# anemo5.net
KiCad netlist of a schematic drawn in EAGLE
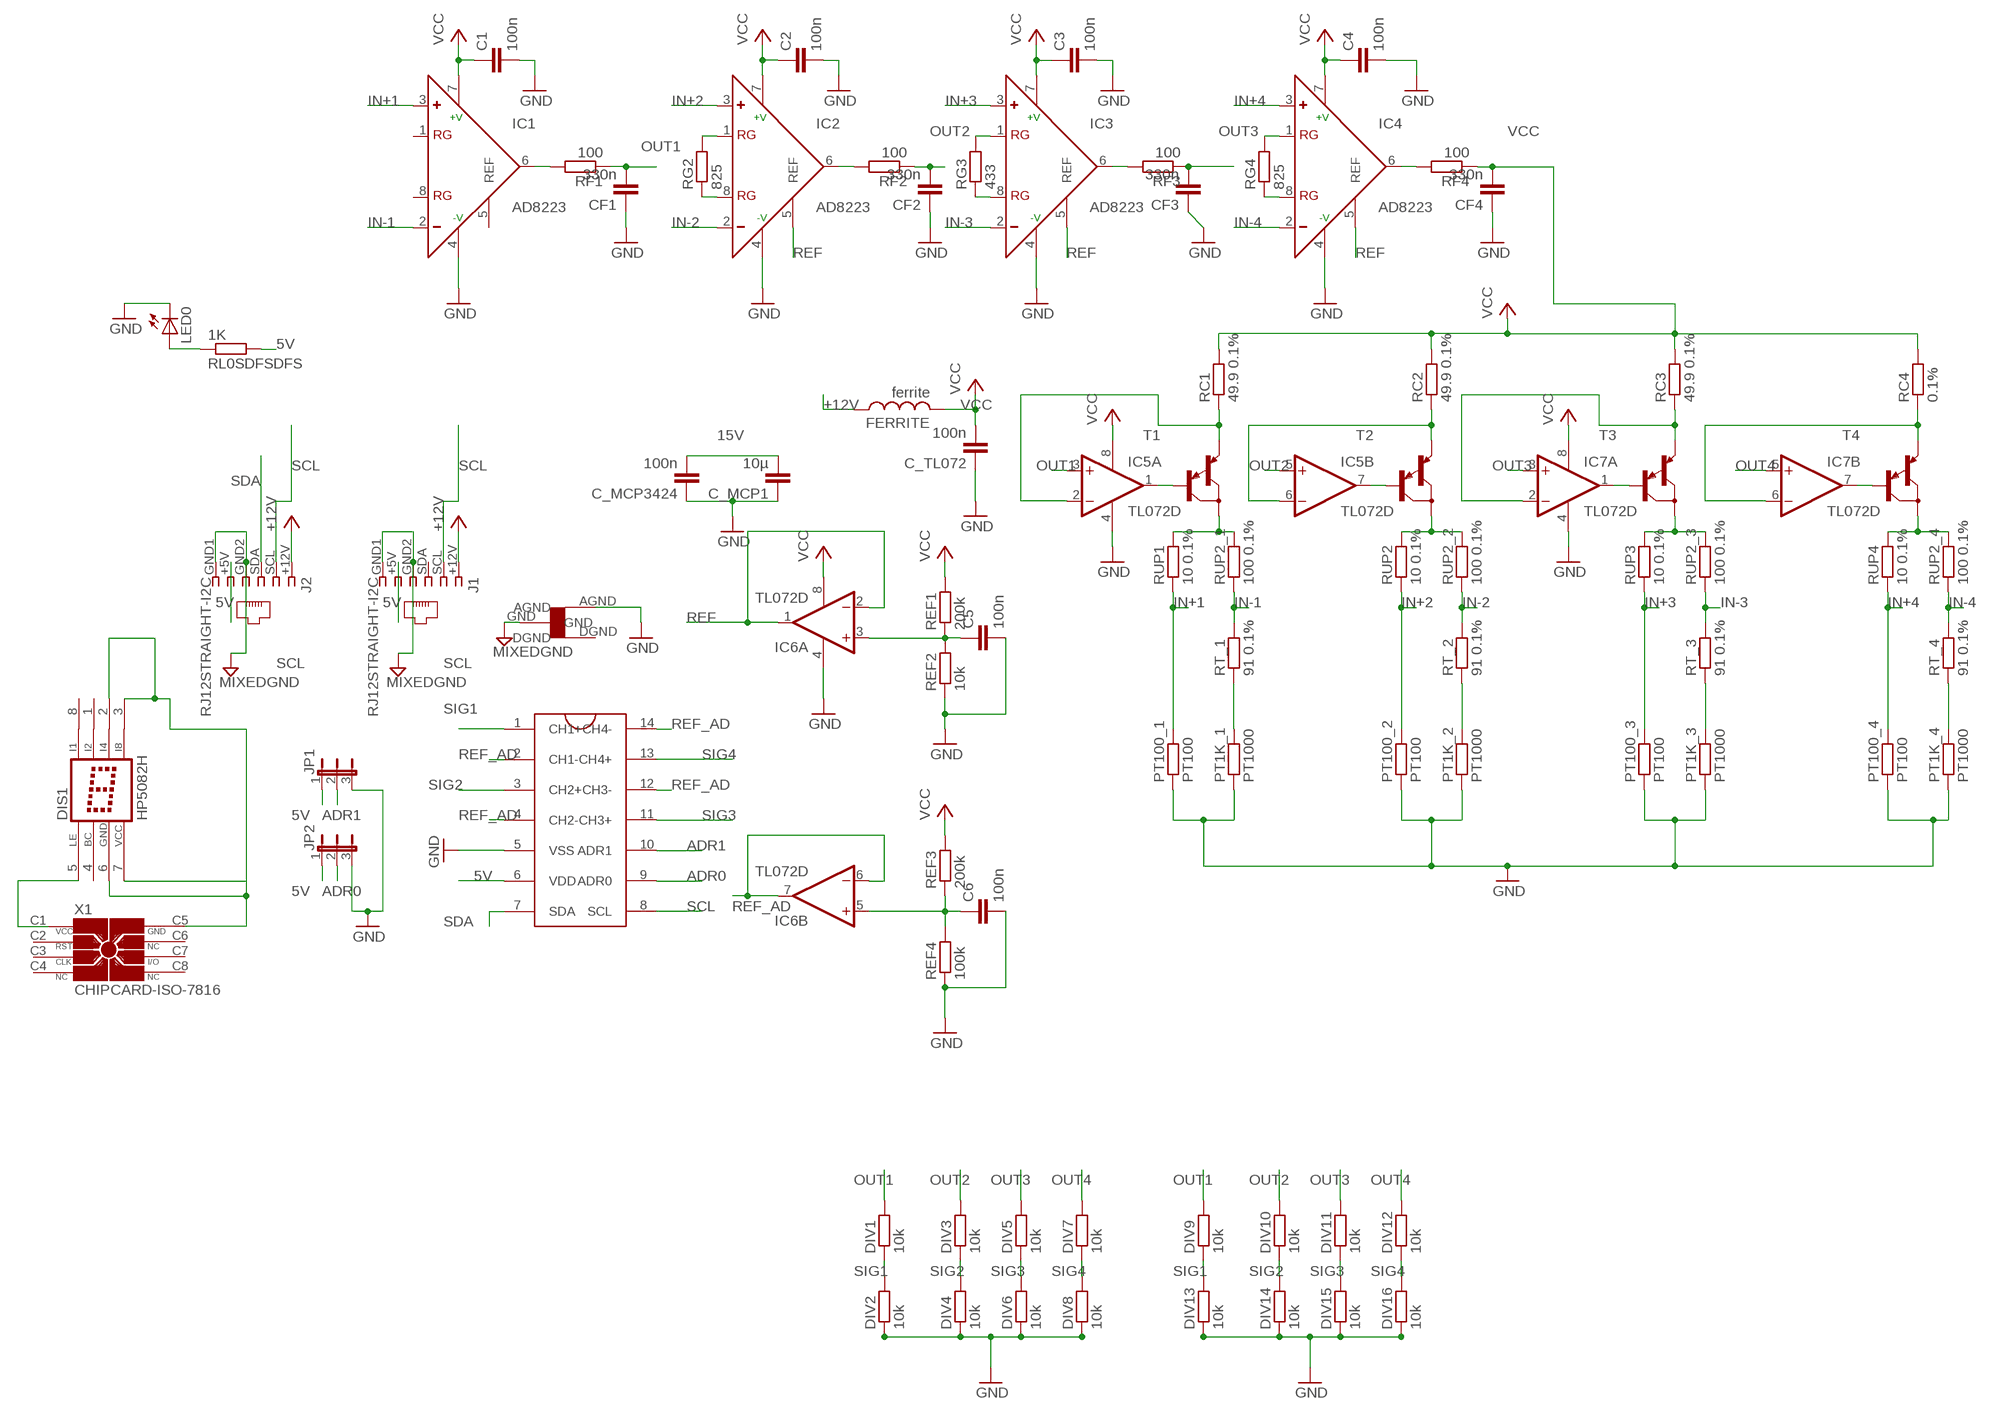
[diagram p0: schematic, sheet 1]

(export (version "E")
  (design (tool "Eeschema 10.0.6"))
  (components
    (comp (ref "C1")
      (value "100n")
      (footprint "eagle-import:C1206")
      (libsource (lib "eagle-import") (part "C-EUC1206"))
    )
    (comp (ref "C2")
      (value "100n")
      (footprint "eagle-import:C1206")
      (libsource (lib "eagle-import") (part "C-EUC1206"))
    )
    (comp (ref "C3")
      (value "100n")
      (footprint "eagle-import:C1206")
      (libsource (lib "eagle-import") (part "C-EUC1206"))
    )
    (comp (ref "C4")
      (value "100n")
      (footprint "eagle-import:C1206")
      (libsource (lib "eagle-import") (part "C-EUC1206"))
    )
    (comp (ref "C5")
      (value "100n")
      (footprint "eagle-import:C1206")
      (libsource (lib "eagle-import") (part "C-EUC1206"))
    )
    (comp (ref "C6")
      (value "100n")
      (footprint "eagle-import:C1206")
      (libsource (lib "eagle-import") (part "C-EUC1206"))
    )
    (comp (ref "CF1")
      (value "330n")
      (footprint "eagle-import:C1206")
      (libsource (lib "eagle-import") (part "C-EUC1206"))
    )
    (comp (ref "CF2")
      (value "330n")
      (footprint "eagle-import:C1206")
      (libsource (lib "eagle-import") (part "C-EUC1206"))
    )
    (comp (ref "CF3")
      (value "330n")
      (footprint "eagle-import:C1206")
      (libsource (lib "eagle-import") (part "C-EUC1206"))
    )
    (comp (ref "CF4")
      (value "330n")
      (footprint "eagle-import:C1206")
      (libsource (lib "eagle-import") (part "C-EUC1206"))
    )
    (comp (ref "C_MCP1")
      (value "10µ")
      (footprint "eagle-import:C1206")
      (libsource (lib "eagle-import") (part "C-EUC1206"))
    )
    (comp (ref "C_MCP3424")
      (value "100n")
      (footprint "eagle-import:C1206")
      (libsource (lib "eagle-import") (part "C-EUC1206"))
    )
    (comp (ref "C_TL072")
      (value "100n")
      (footprint "eagle-import:C1206")
      (libsource (lib "eagle-import") (part "C-EUC1206"))
    )
    (comp (ref "DIS1")
      (value "HP5082H")
      (footprint "eagle-import:HP5082")
      (libsource (lib "eagle-import") (part "HP5082H"))
    )
    (comp (ref "DIV1")
      (value "10k")
      (footprint "eagle-import:M1206")
      (libsource (lib "eagle-import") (part "R-EU_M1206"))
    )
    (comp (ref "DIV2")
      (value "10k")
      (footprint "eagle-import:M1206")
      (libsource (lib "eagle-import") (part "R-EU_M1206"))
    )
    (comp (ref "DIV3")
      (value "10k")
      (footprint "eagle-import:M1206")
      (libsource (lib "eagle-import") (part "R-EU_M1206"))
    )
    (comp (ref "DIV4")
      (value "10k")
      (footprint "eagle-import:M1206")
      (libsource (lib "eagle-import") (part "R-EU_M1206"))
    )
    (comp (ref "DIV5")
      (value "10k")
      (footprint "eagle-import:M1206")
      (libsource (lib "eagle-import") (part "R-EU_M1206"))
    )
    (comp (ref "DIV6")
      (value "10k")
      (footprint "eagle-import:M1206")
      (libsource (lib "eagle-import") (part "R-EU_M1206"))
    )
    (comp (ref "DIV7")
      (value "10k")
      (footprint "eagle-import:M1206")
      (libsource (lib "eagle-import") (part "R-EU_M1206"))
    )
    (comp (ref "DIV8")
      (value "10k")
      (footprint "eagle-import:M1206")
      (libsource (lib "eagle-import") (part "R-EU_M1206"))
    )
    (comp (ref "DIV9")
      (value "10k")
      (footprint "eagle-import:M1206")
      (libsource (lib "eagle-import") (part "R-EU_M1206"))
    )
    (comp (ref "DIV10")
      (value "10k")
      (footprint "eagle-import:M1206")
      (libsource (lib "eagle-import") (part "R-EU_M1206"))
    )
    (comp (ref "DIV11")
      (value "10k")
      (footprint "eagle-import:M1206")
      (libsource (lib "eagle-import") (part "R-EU_M1206"))
    )
    (comp (ref "DIV12")
      (value "10k")
      (footprint "eagle-import:M1206")
      (libsource (lib "eagle-import") (part "R-EU_M1206"))
    )
    (comp (ref "DIV13")
      (value "10k")
      (footprint "eagle-import:M1206")
      (libsource (lib "eagle-import") (part "R-EU_M1206"))
    )
    (comp (ref "DIV14")
      (value "10k")
      (footprint "eagle-import:M1206")
      (libsource (lib "eagle-import") (part "R-EU_M1206"))
    )
    (comp (ref "DIV15")
      (value "10k")
      (footprint "eagle-import:M1206")
      (libsource (lib "eagle-import") (part "R-EU_M1206"))
    )
    (comp (ref "DIV16")
      (value "10k")
      (footprint "eagle-import:M1206")
      (libsource (lib "eagle-import") (part "R-EU_M1206"))
    )
    (comp (ref "FERRITE")
      (value "ferrite")
      (footprint "eagle-import:L3216C")
      (libsource (lib "eagle-import") (part "L-USL3216C"))
    )
    (comp (ref "IC1")
      (value "AD8223")
      (footprint "eagle-import:SO8")
      (fields (field (name "MPN") "AD620AR"))
      (libsource (lib "eagle-import") (part "AD620R"))
    )
    (comp (ref "IC2")
      (value "AD8223")
      (footprint "eagle-import:SO8")
      (fields (field (name "MPN") "AD620AR"))
      (libsource (lib "eagle-import") (part "AD620R"))
    )
    (comp (ref "IC3")
      (value "AD8223")
      (footprint "eagle-import:SO8")
      (fields (field (name "MPN") "AD620AR"))
      (libsource (lib "eagle-import") (part "AD620R"))
    )
    (comp (ref "IC4")
      (value "AD8223")
      (footprint "eagle-import:SO8")
      (fields (field (name "MPN") "AD620AR"))
      (libsource (lib "eagle-import") (part "AD620R"))
    )
    (comp (ref "IC5")
      (value "TL072D")
      (footprint "eagle-import:SO08")
      (libsource (lib "eagle-import") (part "TL072D"))
    )
    (comp (ref "IC6")
      (value "TL072D")
      (footprint "eagle-import:SO08")
      (libsource (lib "eagle-import") (part "TL072D"))
    )
    (comp (ref "IC7")
      (value "TL072D")
      (footprint "eagle-import:SO08")
      (libsource (lib "eagle-import") (part "TL072D"))
    )
    (comp (ref "J1")
      (value "RJ12STRAIGHT-I2C")
      (footprint "eagle-import:RJ12-STRAIGHT-I2C")
      (libsource (lib "eagle-import") (part "RJ12STRAIGHT-I2C"))
    )
    (comp (ref "J2")
      (value "RJ12STRAIGHT-I2C")
      (footprint "eagle-import:RJ12-STRAIGHT-I2C")
      (libsource (lib "eagle-import") (part "RJ12STRAIGHT-I2C"))
    )
    (comp (ref "JP1")
      (value "JP2E")
      (footprint "eagle-import:JP2")
      (libsource (lib "eagle-import") (part "JP2E"))
    )
    (comp (ref "JP2")
      (value "JP2E")
      (footprint "eagle-import:JP2")
      (libsource (lib "eagle-import") (part "JP2E"))
    )
    (comp (ref "LED0")
      (value "LED1206")
      (footprint "eagle-import:LED-1206")
      (libsource (lib "eagle-import") (part "LED1206"))
    )
    (comp (ref "PT1K_1")
      (value "PT1000")
      (footprint "eagle-import:M1206")
      (libsource (lib "eagle-import") (part "R-EU_M1206"))
    )
    (comp (ref "PT1K_2")
      (value "PT1000")
      (footprint "eagle-import:M1206")
      (libsource (lib "eagle-import") (part "R-EU_M1206"))
    )
    (comp (ref "PT1K_3")
      (value "PT1000")
      (footprint "eagle-import:M1206")
      (libsource (lib "eagle-import") (part "R-EU_M1206"))
    )
    (comp (ref "PT1K_4")
      (value "PT1000")
      (footprint "eagle-import:M1206")
      (libsource (lib "eagle-import") (part "R-EU_M1206"))
    )
    (comp (ref "PT100_1")
      (value "PT100")
      (footprint "eagle-import:M1206")
      (libsource (lib "eagle-import") (part "R-EU_M1206"))
    )
    (comp (ref "PT100_2")
      (value "PT100")
      (footprint "eagle-import:M1206")
      (libsource (lib "eagle-import") (part "R-EU_M1206"))
    )
    (comp (ref "PT100_3")
      (value "PT100")
      (footprint "eagle-import:M1206")
      (libsource (lib "eagle-import") (part "R-EU_M1206"))
    )
    (comp (ref "PT100_4")
      (value "PT100")
      (footprint "eagle-import:M1206")
      (libsource (lib "eagle-import") (part "R-EU_M1206"))
    )
    (comp (ref "RC1")
      (value "49.9 0.1%")
      (footprint "eagle-import:M1206")
      (libsource (lib "eagle-import") (part "R-EU_M1206"))
    )
    (comp (ref "RC2")
      (value "49.9 0.1%")
      (footprint "eagle-import:M1206")
      (libsource (lib "eagle-import") (part "R-EU_M1206"))
    )
    (comp (ref "RC3")
      (value "49.9 0.1%")
      (footprint "eagle-import:M1206")
      (libsource (lib "eagle-import") (part "R-EU_M1206"))
    )
    (comp (ref "RC4")
      (value "0.1%")
      (footprint "eagle-import:M1206")
      (libsource (lib "eagle-import") (part "R-EU_M1206"))
    )
    (comp (ref "REF1")
      (value "200k")
      (footprint "eagle-import:M1206")
      (libsource (lib "eagle-import") (part "R-EU_M1206"))
    )
    (comp (ref "REF2")
      (value "10k")
      (footprint "eagle-import:M1206")
      (libsource (lib "eagle-import") (part "R-EU_M1206"))
    )
    (comp (ref "REF3")
      (value "200k")
      (footprint "eagle-import:M1206")
      (libsource (lib "eagle-import") (part "R-EU_M1206"))
    )
    (comp (ref "REF4")
      (value "100k")
      (footprint "eagle-import:M1206")
      (libsource (lib "eagle-import") (part "R-EU_M1206"))
    )
    (comp (ref "RF1")
      (value "100")
      (footprint "eagle-import:M1206")
      (libsource (lib "eagle-import") (part "R-EU_M1206"))
    )
    (comp (ref "RF2")
      (value "100")
      (footprint "eagle-import:M1206")
      (libsource (lib "eagle-import") (part "R-EU_M1206"))
    )
    (comp (ref "RF3")
      (value "100")
      (footprint "eagle-import:M1206")
      (libsource (lib "eagle-import") (part "R-EU_M1206"))
    )
    (comp (ref "RF4")
      (value "100")
      (footprint "eagle-import:M1206")
      (libsource (lib "eagle-import") (part "R-EU_M1206"))
    )
    (comp (ref "RG2")
      (value "825")
      (footprint "eagle-import:M1206")
      (libsource (lib "eagle-import") (part "R-EU_M1206"))
    )
    (comp (ref "RG3")
      (value "433")
      (footprint "eagle-import:M1206")
      (libsource (lib "eagle-import") (part "R-EU_M1206"))
    )
    (comp (ref "RG4")
      (value "825")
      (footprint "eagle-import:M1206")
      (libsource (lib "eagle-import") (part "R-EU_M1206"))
    )
    (comp (ref "RL0SDFSDFS")
      (value "1K")
      (footprint "eagle-import:M1206")
      (libsource (lib "eagle-import") (part "R-EU_M1206"))
    )
    (comp (ref "RT_1")
      (value "91 0.1%")
      (footprint "eagle-import:M1206")
      (libsource (lib "eagle-import") (part "R-EU_M1206"))
    )
    (comp (ref "RT_2")
      (value "91 0.1%")
      (footprint "eagle-import:M1206")
      (libsource (lib "eagle-import") (part "R-EU_M1206"))
    )
    (comp (ref "RT_3")
      (value "91 0.1%")
      (footprint "eagle-import:M1206")
      (libsource (lib "eagle-import") (part "R-EU_M1206"))
    )
    (comp (ref "RT_4")
      (value "91 0.1%")
      (footprint "eagle-import:M1206")
      (libsource (lib "eagle-import") (part "R-EU_M1206"))
    )
    (comp (ref "RUP1")
      (value "10 0.1%")
      (footprint "eagle-import:M1206")
      (libsource (lib "eagle-import") (part "R-EU_M1206"))
    )
    (comp (ref "RUP2")
      (value "10 0.1%")
      (footprint "eagle-import:M1206")
      (libsource (lib "eagle-import") (part "R-EU_M1206"))
    )
    (comp (ref "RUP2_1")
      (value "100 0.1%")
      (footprint "eagle-import:M1206")
      (libsource (lib "eagle-import") (part "R-EU_M1206"))
    )
    (comp (ref "RUP2_2")
      (value "100 0.1%")
      (footprint "eagle-import:M1206")
      (libsource (lib "eagle-import") (part "R-EU_M1206"))
    )
    (comp (ref "RUP2_3")
      (value "100 0.1%")
      (footprint "eagle-import:M1206")
      (libsource (lib "eagle-import") (part "R-EU_M1206"))
    )
    (comp (ref "RUP2_4")
      (value "100 0.1%")
      (footprint "eagle-import:M1206")
      (libsource (lib "eagle-import") (part "R-EU_M1206"))
    )
    (comp (ref "RUP3")
      (value "10 0.1%")
      (footprint "eagle-import:M1206")
      (libsource (lib "eagle-import") (part "R-EU_M1206"))
    )
    (comp (ref "RUP4")
      (value "10 0.1%")
      (footprint "eagle-import:M1206")
      (libsource (lib "eagle-import") (part "R-EU_M1206"))
    )
    (comp (ref "T1")
      (value "MMBTA64LT1-PNP_DARL-SOT23-BEC")
      (footprint "eagle-import:SOT23-BEC")
      (libsource (lib "eagle-import") (part "-PNP_DARL-SOT23-BECMMBTA64LT1"))
    )
    (comp (ref "T2")
      (value "MMBTA64LT1-PNP_DARL-SOT23-BEC")
      (footprint "eagle-import:SOT23-BEC")
      (libsource (lib "eagle-import") (part "-PNP_DARL-SOT23-BECMMBTA64LT1"))
    )
    (comp (ref "T3")
      (value "MMBTA64LT1-PNP_DARL-SOT23-BEC")
      (footprint "eagle-import:SOT23-BEC")
      (libsource (lib "eagle-import") (part "-PNP_DARL-SOT23-BECMMBTA64LT1"))
    )
    (comp (ref "T4")
      (value "MMBTA64LT1-PNP_DARL-SOT23-BEC")
      (footprint "eagle-import:SOT23-BEC")
      (libsource (lib "eagle-import") (part "-PNP_DARL-SOT23-BECMMBTA64LT1"))
    )
    (comp (ref "U$1")
      (value "MCP3424(SO14)")
      (footprint "eagle-import:14LDSOIC")
      (libsource (lib "eagle-import") (part "MCP3424(SO14)"))
    )
    (comp (ref "U$2")
      (value "STARGND")
      (footprint "eagle-import:STAR")
      (libsource (lib "eagle-import") (part "STARGND"))
    )
    (comp (ref "X1")
      (value "CHIPCARD-ISO-7816")
      (footprint "eagle-import:ISO7816")
      (libsource (lib "eagle-import") (part "CHIPCARD-ISO-7816"))
    )
  )
  (nets
    (net (code "1") (name "+12V") (class "Default")
      (node (ref "FERRITE") (pin "1") (pinfunction "1_1") (pintype "passive"))
      (node (ref "J1") (pin "+12V") (pinfunction "1_+12V") (pintype "bidirectional"))
      (node (ref "J2") (pin "+12V") (pinfunction "1_+12V") (pintype "bidirectional"))
    )
    (net (code "2") (name "/5V") (class "Default")
      (node (ref "J1") (pin "+5V") (pinfunction "5_+5V") (pintype "bidirectional"))
      (node (ref "J2") (pin "+5V") (pinfunction "5_+5V") (pintype "bidirectional"))
      (node (ref "JP1") (pin "1") (pinfunction "1_1") (pintype "passive"))
      (node (ref "JP2") (pin "1") (pinfunction "1_1") (pintype "passive"))
      (node (ref "RL0SDFSDFS") (pin "2") (pinfunction "2_2") (pintype "passive"))
      (node (ref "U$1") (pin "6") (pinfunction "VDD_6") (pintype "bidirectional"))
    )
    (net (code "3") (name "/15V") (class "Default")
      (node (ref "C_MCP1") (pin "2") (pinfunction "2_2") (pintype "passive"))
      (node (ref "C_MCP3424") (pin "2") (pinfunction "2_2") (pintype "passive"))
    )
    (net (code "4") (name "/ADR0") (class "Default")
      (node (ref "JP2") (pin "2") (pinfunction "2_2") (pintype "passive"))
      (node (ref "U$1") (pin "9") (pinfunction "ADR0_9") (pintype "bidirectional"))
    )
    (net (code "5") (name "/ADR1") (class "Default")
      (node (ref "JP1") (pin "2") (pinfunction "2_2") (pintype "passive"))
      (node (ref "U$1") (pin "10") (pinfunction "ADR1_10") (pintype "bidirectional"))
    )
    (net (code "6") (name "/IN+1") (class "Default")
      (node (ref "IC1") (pin "3") (pinfunction "+_3") (pintype "input"))
      (node (ref "PT100_1") (pin "2") (pinfunction "2_2") (pintype "passive"))
      (node (ref "RUP1") (pin "1") (pinfunction "1_1") (pintype "passive"))
    )
    (net (code "7") (name "/IN+2") (class "Default")
      (node (ref "IC2") (pin "3") (pinfunction "+_3") (pintype "input"))
      (node (ref "PT100_2") (pin "2") (pinfunction "2_2") (pintype "passive"))
      (node (ref "RUP2") (pin "1") (pinfunction "1_1") (pintype "passive"))
    )
    (net (code "8") (name "/IN+3") (class "Default")
      (node (ref "IC3") (pin "3") (pinfunction "+_3") (pintype "input"))
      (node (ref "PT100_3") (pin "2") (pinfunction "2_2") (pintype "passive"))
      (node (ref "RUP3") (pin "1") (pinfunction "1_1") (pintype "passive"))
    )
    (net (code "9") (name "/IN+4") (class "Default")
      (node (ref "IC4") (pin "3") (pinfunction "+_3") (pintype "input"))
      (node (ref "PT100_4") (pin "2") (pinfunction "2_2") (pintype "passive"))
      (node (ref "RUP4") (pin "1") (pinfunction "1_1") (pintype "passive"))
    )
    (net (code "10") (name "/IN-1") (class "Default")
      (node (ref "IC1") (pin "2") (pinfunction "-_2") (pintype "input"))
      (node (ref "RT_1") (pin "2") (pinfunction "2_2") (pintype "passive"))
      (node (ref "RUP2_1") (pin "1") (pinfunction "1_1") (pintype "passive"))
    )
    (net (code "11") (name "/IN-2") (class "Default")
      (node (ref "IC2") (pin "2") (pinfunction "-_2") (pintype "input"))
      (node (ref "RT_2") (pin "2") (pinfunction "2_2") (pintype "passive"))
      (node (ref "RUP2_2") (pin "1") (pinfunction "1_1") (pintype "passive"))
    )
    (net (code "12") (name "/IN-3") (class "Default")
      (node (ref "IC3") (pin "2") (pinfunction "-_2") (pintype "input"))
      (node (ref "RT_3") (pin "2") (pinfunction "2_2") (pintype "passive"))
      (node (ref "RUP2_3") (pin "1") (pinfunction "1_1") (pintype "passive"))
    )
    (net (code "13") (name "/IN-4") (class "Default")
      (node (ref "IC4") (pin "2") (pinfunction "-_2") (pintype "input"))
      (node (ref "RT_4") (pin "2") (pinfunction "2_2") (pintype "passive"))
      (node (ref "RUP2_4") (pin "1") (pinfunction "1_1") (pintype "passive"))
    )
    (net (code "14") (name "/OUT1") (class "Default")
      (node (ref "CF1") (pin "2") (pinfunction "2_2") (pintype "passive"))
      (node (ref "DIV1") (pin "2") (pinfunction "2_2") (pintype "passive"))
      (node (ref "DIV9") (pin "2") (pinfunction "2_2") (pintype "passive"))
      (node (ref "IC5") (pin "3") (pinfunction "+IN_3") (pintype "input"))
      (node (ref "RF1") (pin "1") (pinfunction "1_1") (pintype "passive"))
    )
    (net (code "15") (name "/OUT2") (class "Default")
      (node (ref "CF2") (pin "2") (pinfunction "2_2") (pintype "passive"))
      (node (ref "DIV10") (pin "2") (pinfunction "2_2") (pintype "passive"))
      (node (ref "DIV3") (pin "2") (pinfunction "2_2") (pintype "passive"))
      (node (ref "IC5") (pin "5") (pinfunction "+IN_5") (pintype "input"))
      (node (ref "RF2") (pin "1") (pinfunction "1_1") (pintype "passive"))
    )
    (net (code "16") (name "/OUT3") (class "Default")
      (node (ref "CF3") (pin "2") (pinfunction "2_2") (pintype "passive"))
      (node (ref "DIV11") (pin "2") (pinfunction "2_2") (pintype "passive"))
      (node (ref "DIV5") (pin "2") (pinfunction "2_2") (pintype "passive"))
      (node (ref "IC7") (pin "3") (pinfunction "+IN_3") (pintype "input"))
      (node (ref "RF3") (pin "1") (pinfunction "1_1") (pintype "passive"))
    )
    (net (code "17") (name "/OUT4") (class "Default")
      (node (ref "DIV12") (pin "2") (pinfunction "2_2") (pintype "passive"))
      (node (ref "DIV7") (pin "2") (pinfunction "2_2") (pintype "passive"))
      (node (ref "IC7") (pin "5") (pinfunction "+IN_5") (pintype "input"))
    )
    (net (code "18") (name "/REF") (class "Default")
      (node (ref "IC2") (pin "5") (pinfunction "REF_5") (pintype "passive"))
      (node (ref "IC3") (pin "5") (pinfunction "REF_5") (pintype "passive"))
      (node (ref "IC4") (pin "5") (pinfunction "REF_5") (pintype "passive"))
      (node (ref "IC6") (pin "1") (pinfunction "OUT_1") (pintype "output"))
      (node (ref "IC6") (pin "2") (pinfunction "-IN_2") (pintype "input"))
    )
    (net (code "19") (name "/REF_AD") (class "Default")
      (node (ref "IC6") (pin "6") (pinfunction "-IN_6") (pintype "input"))
      (node (ref "IC6") (pin "7") (pinfunction "OUT_7") (pintype "output"))
      (node (ref "U$1") (pin "12") (pinfunction "CH3-_12") (pintype "bidirectional"))
      (node (ref "U$1") (pin "14") (pinfunction "CH4-_14") (pintype "bidirectional"))
      (node (ref "U$1") (pin "2") (pinfunction "CH1-_2") (pintype "bidirectional"))
      (node (ref "U$1") (pin "4") (pinfunction "CH2-_4") (pintype "bidirectional"))
    )
    (net (code "20") (name "/SCL") (class "Default")
      (node (ref "J1") (pin "SCL") (pinfunction "2_SCL") (pintype "bidirectional"))
      (node (ref "J2") (pin "SCL") (pinfunction "2_SCL") (pintype "bidirectional"))
      (node (ref "U$1") (pin "8") (pinfunction "SCL_8") (pintype "bidirectional"))
    )
    (net (code "21") (name "/SDA") (class "Default")
      (node (ref "J2") (pin "SDA") (pinfunction "3_SDA") (pintype "bidirectional"))
      (node (ref "U$1") (pin "7") (pinfunction "SDA_7") (pintype "bidirectional"))
    )
    (net (code "22") (name "/SIG1") (class "Default")
      (node (ref "DIV1") (pin "1") (pinfunction "1_1") (pintype "passive"))
      (node (ref "DIV13") (pin "2") (pinfunction "2_2") (pintype "passive"))
      (node (ref "DIV2") (pin "2") (pinfunction "2_2") (pintype "passive"))
      (node (ref "DIV9") (pin "1") (pinfunction "1_1") (pintype "passive"))
      (node (ref "U$1") (pin "1") (pinfunction "CH1+_1") (pintype "bidirectional"))
    )
    (net (code "23") (name "/SIG2") (class "Default")
      (node (ref "DIV10") (pin "1") (pinfunction "1_1") (pintype "passive"))
      (node (ref "DIV14") (pin "2") (pinfunction "2_2") (pintype "passive"))
      (node (ref "DIV3") (pin "1") (pinfunction "1_1") (pintype "passive"))
      (node (ref "DIV4") (pin "2") (pinfunction "2_2") (pintype "passive"))
      (node (ref "U$1") (pin "3") (pinfunction "CH2+_3") (pintype "bidirectional"))
    )
    (net (code "24") (name "/SIG3") (class "Default")
      (node (ref "DIV11") (pin "1") (pinfunction "1_1") (pintype "passive"))
      (node (ref "DIV15") (pin "2") (pinfunction "2_2") (pintype "passive"))
      (node (ref "DIV5") (pin "1") (pinfunction "1_1") (pintype "passive"))
      (node (ref "DIV6") (pin "2") (pinfunction "2_2") (pintype "passive"))
      (node (ref "U$1") (pin "11") (pinfunction "CH3+_11") (pintype "bidirectional"))
    )
    (net (code "25") (name "/SIG4") (class "Default")
      (node (ref "DIV12") (pin "1") (pinfunction "1_1") (pintype "passive"))
      (node (ref "DIV16") (pin "2") (pinfunction "2_2") (pintype "passive"))
      (node (ref "DIV7") (pin "1") (pinfunction "1_1") (pintype "passive"))
      (node (ref "DIV8") (pin "2") (pinfunction "2_2") (pintype "passive"))
      (node (ref "U$1") (pin "13") (pinfunction "CH4+_13") (pintype "bidirectional"))
    )
    (net (code "26") (name "GND") (class "Default")
      (node (ref "C1") (pin "2") (pinfunction "2_2") (pintype "passive"))
      (node (ref "C2") (pin "2") (pinfunction "2_2") (pintype "passive"))
      (node (ref "C3") (pin "2") (pinfunction "2_2") (pintype "passive"))
      (node (ref "C4") (pin "2") (pinfunction "2_2") (pintype "passive"))
      (node (ref "C5") (pin "2") (pinfunction "2_2") (pintype "passive"))
      (node (ref "C6") (pin "2") (pinfunction "2_2") (pintype "passive"))
      (node (ref "CF1") (pin "1") (pinfunction "1_1") (pintype "passive"))
      (node (ref "CF2") (pin "1") (pinfunction "1_1") (pintype "passive"))
      (node (ref "CF3") (pin "1") (pinfunction "1_1") (pintype "passive"))
      (node (ref "CF4") (pin "1") (pinfunction "1_1") (pintype "passive"))
      (node (ref "C_MCP1") (pin "1") (pinfunction "1_1") (pintype "passive"))
      (node (ref "C_MCP3424") (pin "1") (pinfunction "1_1") (pintype "passive"))
      (node (ref "C_TL072") (pin "1") (pinfunction "1_1") (pintype "passive"))
      (node (ref "DIV13") (pin "1") (pinfunction "1_1") (pintype "passive"))
      (node (ref "DIV14") (pin "1") (pinfunction "1_1") (pintype "passive"))
      (node (ref "DIV15") (pin "1") (pinfunction "1_1") (pintype "passive"))
      (node (ref "DIV16") (pin "1") (pinfunction "1_1") (pintype "passive"))
      (node (ref "DIV2") (pin "1") (pinfunction "1_1") (pintype "passive"))
      (node (ref "DIV4") (pin "1") (pinfunction "1_1") (pintype "passive"))
      (node (ref "DIV6") (pin "1") (pinfunction "1_1") (pintype "passive"))
      (node (ref "DIV8") (pin "1") (pinfunction "1_1") (pintype "passive"))
      (node (ref "IC1") (pin "4") (pinfunction "-V_4") (pintype "power_in"))
      (node (ref "IC2") (pin "4") (pinfunction "-V_4") (pintype "power_in"))
      (node (ref "IC3") (pin "4") (pinfunction "-V_4") (pintype "power_in"))
      (node (ref "IC4") (pin "4") (pinfunction "-V_4") (pintype "power_in"))
      (node (ref "IC5") (pin "4") (pinfunction "V-_4") (pintype "power_in"))
      (node (ref "IC6") (pin "4") (pinfunction "V-_4") (pintype "power_in"))
      (node (ref "IC7") (pin "4") (pinfunction "V-_4") (pintype "power_in"))
      (node (ref "JP1") (pin "3") (pinfunction "3_3") (pintype "passive"))
      (node (ref "JP2") (pin "3") (pinfunction "3_3") (pintype "passive"))
      (node (ref "LED0") (pin "C") (pinfunction "C_C") (pintype "passive"))
      (node (ref "PT100_1") (pin "1") (pinfunction "1_1") (pintype "passive"))
      (node (ref "PT100_2") (pin "1") (pinfunction "1_1") (pintype "passive"))
      (node (ref "PT100_3") (pin "1") (pinfunction "1_1") (pintype "passive"))
      (node (ref "PT100_4") (pin "1") (pinfunction "1_1") (pintype "passive"))
      (node (ref "PT1K_1") (pin "1") (pinfunction "1_1") (pintype "passive"))
      (node (ref "PT1K_2") (pin "1") (pinfunction "1_1") (pintype "passive"))
      (node (ref "PT1K_3") (pin "1") (pinfunction "1_1") (pintype "passive"))
      (node (ref "PT1K_4") (pin "1") (pinfunction "1_1") (pintype "passive"))
      (node (ref "REF2") (pin "1") (pinfunction "1_1") (pintype "passive"))
      (node (ref "REF4") (pin "1") (pinfunction "1_1") (pintype "passive"))
      (node (ref "U$1") (pin "5") (pinfunction "VSS_5") (pintype "bidirectional"))
      (node (ref "U$2") (pin "AGND") (pinfunction "AGND_AGND") (pintype "output"))
    )
    (net (code "27") (name "MIXEDGND") (class "Default")
      (node (ref "J1") (pin "GND1") (pinfunction "6_GND1") (pintype "bidirectional"))
      (node (ref "J1") (pin "GND2") (pinfunction "4_GND2") (pintype "bidirectional"))
      (node (ref "J2") (pin "GND1") (pinfunction "6_GND1") (pintype "bidirectional"))
      (node (ref "J2") (pin "GND2") (pinfunction "4_GND2") (pintype "bidirectional"))
      (node (ref "U$2") (pin "GND") (pinfunction "GND_GND") (pintype "power_in"))
    )
    (net (code "28") (name "Net-(DIS1-GND)") (class "Default")
      (node (ref "DIS1") (pin "2") (pinfunction "I4_2") (pintype "input"))
      (node (ref "DIS1") (pin "3") (pinfunction "I8_3") (pintype "input"))
      (node (ref "DIS1") (pin "6") (pinfunction "GND_6") (pintype "power_in"))
      (node (ref "DIS1") (pin "7") (pinfunction "VCC_7") (pintype "power_in"))
      (node (ref "X1") (pin "C5") (pinfunction "GND_C5") (pintype "passive"))
    )
    (net (code "29") (name "Net-(IC1-OUT)") (class "Default")
      (node (ref "IC1") (pin "6") (pinfunction "OUT_6") (pintype "output"))
      (node (ref "RF1") (pin "2") (pinfunction "2_2") (pintype "passive"))
    )
    (net (code "30") (name "Net-(IC2-OUT)") (class "Default")
      (node (ref "IC2") (pin "6") (pinfunction "OUT_6") (pintype "output"))
      (node (ref "RF2") (pin "2") (pinfunction "2_2") (pintype "passive"))
    )
    (net (code "31") (name "Net-(IC2-RG-Pad1)") (class "Default")
      (node (ref "IC2") (pin "1") (pinfunction "RG_1") (pintype "passive"))
      (node (ref "RG2") (pin "2") (pinfunction "2_2") (pintype "passive"))
    )
    (net (code "32") (name "Net-(IC2-RG-Pad8)") (class "Default")
      (node (ref "IC2") (pin "8") (pinfunction "RG_8") (pintype "passive"))
      (node (ref "RG2") (pin "1") (pinfunction "1_1") (pintype "passive"))
    )
    (net (code "33") (name "Net-(IC3-OUT)") (class "Default")
      (node (ref "IC3") (pin "6") (pinfunction "OUT_6") (pintype "output"))
      (node (ref "RF3") (pin "2") (pinfunction "2_2") (pintype "passive"))
    )
    (net (code "34") (name "Net-(IC3-RG-Pad1)") (class "Default")
      (node (ref "IC3") (pin "1") (pinfunction "RG_1") (pintype "passive"))
      (node (ref "RG3") (pin "2") (pinfunction "2_2") (pintype "passive"))
    )
    (net (code "35") (name "Net-(IC3-RG-Pad8)") (class "Default")
      (node (ref "IC3") (pin "8") (pinfunction "RG_8") (pintype "passive"))
      (node (ref "RG3") (pin "1") (pinfunction "1_1") (pintype "passive"))
    )
    (net (code "36") (name "Net-(IC4-OUT)") (class "Default")
      (node (ref "IC4") (pin "6") (pinfunction "OUT_6") (pintype "output"))
      (node (ref "RF4") (pin "2") (pinfunction "2_2") (pintype "passive"))
    )
    (net (code "37") (name "Net-(IC4-RG-Pad1)") (class "Default")
      (node (ref "IC4") (pin "1") (pinfunction "RG_1") (pintype "passive"))
      (node (ref "RG4") (pin "2") (pinfunction "2_2") (pintype "passive"))
    )
    (net (code "38") (name "Net-(IC4-RG-Pad8)") (class "Default")
      (node (ref "IC4") (pin "8") (pinfunction "RG_8") (pintype "passive"))
      (node (ref "RG4") (pin "1") (pinfunction "1_1") (pintype "passive"))
    )
    (net (code "39") (name "Net-(IC5A--IN)") (class "Default")
      (node (ref "IC5") (pin "2") (pinfunction "-IN_2") (pintype "input"))
      (node (ref "RC1") (pin "1") (pinfunction "1_1") (pintype "passive"))
      (node (ref "T1") (pin "E") (pinfunction "E_E") (pintype "passive"))
    )
    (net (code "40") (name "Net-(IC5A-OUT)") (class "Default")
      (node (ref "IC5") (pin "1") (pinfunction "OUT_1") (pintype "output"))
      (node (ref "T1") (pin "B") (pinfunction "B_B") (pintype "passive"))
    )
    (net (code "41") (name "Net-(IC5B--IN)") (class "Default")
      (node (ref "IC5") (pin "6") (pinfunction "-IN_6") (pintype "input"))
      (node (ref "RC2") (pin "1") (pinfunction "1_1") (pintype "passive"))
      (node (ref "T2") (pin "E") (pinfunction "E_E") (pintype "passive"))
    )
    (net (code "42") (name "Net-(IC5B-OUT)") (class "Default")
      (node (ref "IC5") (pin "7") (pinfunction "OUT_7") (pintype "output"))
      (node (ref "T2") (pin "B") (pinfunction "B_B") (pintype "passive"))
    )
    (net (code "43") (name "Net-(IC6A-+IN)") (class "Default")
      (node (ref "C5") (pin "1") (pinfunction "1_1") (pintype "passive"))
      (node (ref "IC6") (pin "3") (pinfunction "+IN_3") (pintype "input"))
      (node (ref "REF1") (pin "1") (pinfunction "1_1") (pintype "passive"))
      (node (ref "REF2") (pin "2") (pinfunction "2_2") (pintype "passive"))
    )
    (net (code "44") (name "Net-(IC6B-+IN)") (class "Default")
      (node (ref "C6") (pin "1") (pinfunction "1_1") (pintype "passive"))
      (node (ref "IC6") (pin "5") (pinfunction "+IN_5") (pintype "input"))
      (node (ref "REF3") (pin "1") (pinfunction "1_1") (pintype "passive"))
      (node (ref "REF4") (pin "2") (pinfunction "2_2") (pintype "passive"))
    )
    (net (code "45") (name "Net-(IC7A--IN)") (class "Default")
      (node (ref "IC7") (pin "2") (pinfunction "-IN_2") (pintype "input"))
      (node (ref "RC3") (pin "1") (pinfunction "1_1") (pintype "passive"))
      (node (ref "T3") (pin "E") (pinfunction "E_E") (pintype "passive"))
    )
    (net (code "46") (name "Net-(IC7A-OUT)") (class "Default")
      (node (ref "IC7") (pin "1") (pinfunction "OUT_1") (pintype "output"))
      (node (ref "T3") (pin "B") (pinfunction "B_B") (pintype "passive"))
    )
    (net (code "47") (name "Net-(IC7B--IN)") (class "Default")
      (node (ref "IC7") (pin "6") (pinfunction "-IN_6") (pintype "input"))
      (node (ref "RC4") (pin "1") (pinfunction "1_1") (pintype "passive"))
      (node (ref "T4") (pin "E") (pinfunction "E_E") (pintype "passive"))
    )
    (net (code "48") (name "Net-(IC7B-OUT)") (class "Default")
      (node (ref "IC7") (pin "7") (pinfunction "OUT_7") (pintype "output"))
      (node (ref "T4") (pin "B") (pinfunction "B_B") (pintype "passive"))
    )
    (net (code "49") (name "Net-(LED0-PadA)") (class "Default")
      (node (ref "LED0") (pin "A") (pinfunction "A_A") (pintype "passive"))
      (node (ref "RL0SDFSDFS") (pin "1") (pinfunction "1_1") (pintype "passive"))
    )
    (net (code "50") (name "Net-(PT1K_1-Pad2)") (class "Default")
      (node (ref "PT1K_1") (pin "2") (pinfunction "2_2") (pintype "passive"))
      (node (ref "RT_1") (pin "1") (pinfunction "1_1") (pintype "passive"))
    )
    (net (code "51") (name "Net-(PT1K_2-Pad2)") (class "Default")
      (node (ref "PT1K_2") (pin "2") (pinfunction "2_2") (pintype "passive"))
      (node (ref "RT_2") (pin "1") (pinfunction "1_1") (pintype "passive"))
    )
    (net (code "52") (name "Net-(PT1K_3-Pad2)") (class "Default")
      (node (ref "PT1K_3") (pin "2") (pinfunction "2_2") (pintype "passive"))
      (node (ref "RT_3") (pin "1") (pinfunction "1_1") (pintype "passive"))
    )
    (net (code "53") (name "Net-(PT1K_4-Pad2)") (class "Default")
      (node (ref "PT1K_4") (pin "2") (pinfunction "2_2") (pintype "passive"))
      (node (ref "RT_4") (pin "1") (pinfunction "1_1") (pintype "passive"))
    )
    (net (code "54") (name "Net-(RUP1-Pad2)") (class "Default")
      (node (ref "RUP1") (pin "2") (pinfunction "2_2") (pintype "passive"))
      (node (ref "RUP2_1") (pin "2") (pinfunction "2_2") (pintype "passive"))
      (node (ref "T1") (pin "C") (pinfunction "C_C") (pintype "passive"))
    )
    (net (code "55") (name "Net-(RUP2-Pad2)") (class "Default")
      (node (ref "RUP2") (pin "2") (pinfunction "2_2") (pintype "passive"))
      (node (ref "RUP2_2") (pin "2") (pinfunction "2_2") (pintype "passive"))
      (node (ref "T2") (pin "C") (pinfunction "C_C") (pintype "passive"))
    )
    (net (code "56") (name "Net-(RUP2_3-Pad2)") (class "Default")
      (node (ref "RUP2_3") (pin "2") (pinfunction "2_2") (pintype "passive"))
      (node (ref "RUP3") (pin "2") (pinfunction "2_2") (pintype "passive"))
      (node (ref "T3") (pin "C") (pinfunction "C_C") (pintype "passive"))
    )
    (net (code "57") (name "Net-(RUP2_4-Pad2)") (class "Default")
      (node (ref "RUP2_4") (pin "2") (pinfunction "2_2") (pintype "passive"))
      (node (ref "RUP4") (pin "2") (pinfunction "2_2") (pintype "passive"))
      (node (ref "T4") (pin "C") (pinfunction "C_C") (pintype "passive"))
    )
    (net (code "58") (name "VCC") (class "Default")
      (node (ref "C1") (pin "1") (pinfunction "1_1") (pintype "passive"))
      (node (ref "C2") (pin "1") (pinfunction "1_1") (pintype "passive"))
      (node (ref "C3") (pin "1") (pinfunction "1_1") (pintype "passive"))
      (node (ref "C4") (pin "1") (pinfunction "1_1") (pintype "passive"))
      (node (ref "CF4") (pin "2") (pinfunction "2_2") (pintype "passive"))
      (node (ref "C_TL072") (pin "2") (pinfunction "2_2") (pintype "passive"))
      (node (ref "FERRITE") (pin "2") (pinfunction "2_2") (pintype "passive"))
      (node (ref "IC1") (pin "7") (pinfunction "+V_7") (pintype "power_in"))
      (node (ref "IC2") (pin "7") (pinfunction "+V_7") (pintype "power_in"))
      (node (ref "IC3") (pin "7") (pinfunction "+V_7") (pintype "power_in"))
      (node (ref "IC4") (pin "7") (pinfunction "+V_7") (pintype "power_in"))
      (node (ref "IC5") (pin "8") (pinfunction "V+_8") (pintype "power_in"))
      (node (ref "IC6") (pin "8") (pinfunction "V+_8") (pintype "power_in"))
      (node (ref "IC7") (pin "8") (pinfunction "V+_8") (pintype "power_in"))
      (node (ref "RC1") (pin "2") (pinfunction "2_2") (pintype "passive"))
      (node (ref "RC2") (pin "2") (pinfunction "2_2") (pintype "passive"))
      (node (ref "RC3") (pin "2") (pinfunction "2_2") (pintype "passive"))
      (node (ref "RC4") (pin "2") (pinfunction "2_2") (pintype "passive"))
      (node (ref "REF1") (pin "2") (pinfunction "2_2") (pintype "passive"))
      (node (ref "REF3") (pin "2") (pinfunction "2_2") (pintype "passive"))
      (node (ref "RF4") (pin "1") (pinfunction "1_1") (pintype "passive"))
    )
    (net (code "59") (name "unconnected-(DIS1-BC-Pad4)") (class "Default")
      (node (ref "DIS1") (pin "4") (pinfunction "BC_4") (pintype "input"))
    )
    (net (code "60") (name "unconnected-(DIS1-I1-Pad8)") (class "Default")
      (node (ref "DIS1") (pin "8") (pinfunction "I1_8") (pintype "input"))
    )
    (net (code "61") (name "unconnected-(DIS1-I2-Pad1)") (class "Default")
      (node (ref "DIS1") (pin "1") (pinfunction "I2_1") (pintype "input"))
    )
    (net (code "62") (name "unconnected-(DIS1-LE-Pad5)") (class "Default")
      (node (ref "DIS1") (pin "5") (pinfunction "LE_5") (pintype "input"))
    )
    (net (code "63") (name "unconnected-(IC1-REF-Pad5)") (class "Default")
      (node (ref "IC1") (pin "5") (pinfunction "REF_5") (pintype "passive"))
    )
    (net (code "64") (name "unconnected-(IC1-RG-Pad1)") (class "Default")
      (node (ref "IC1") (pin "1") (pinfunction "RG_1") (pintype "passive"))
    )
    (net (code "65") (name "unconnected-(IC1-RG-Pad8)") (class "Default")
      (node (ref "IC1") (pin "8") (pinfunction "RG_8") (pintype "passive"))
    )
    (net (code "66") (name "unconnected-(J1-3-PadSDA)") (class "Default")
      (node (ref "J1") (pin "SDA") (pinfunction "3_SDA") (pintype "bidirectional"))
    )
    (net (code "67") (name "unconnected-(U$2-PadDGND)") (class "Default")
      (node (ref "U$2") (pin "DGND") (pinfunction "DGND_DGND") (pintype "output"))
    )
    (net (code "68") (name "unconnected-(X1-CLK-PadC3)") (class "Default")
      (node (ref "X1") (pin "C3") (pinfunction "CLK_C3") (pintype "passive"))
    )
    (net (code "69") (name "unconnected-(X1-I{slash}O-PadC7)") (class "Default")
      (node (ref "X1") (pin "C7") (pinfunction "I/O_C7") (pintype "passive"))
    )
    (net (code "70") (name "unconnected-(X1-NC-PadC4)") (class "Default")
      (node (ref "X1") (pin "C4") (pinfunction "NC_C4") (pintype "passive"))
    )
    (net (code "71") (name "unconnected-(X1-NC-PadC6)") (class "Default")
      (node (ref "X1") (pin "C6") (pinfunction "NC_C6") (pintype "passive"))
    )
    (net (code "72") (name "unconnected-(X1-NC-PadC8)") (class "Default")
      (node (ref "X1") (pin "C8") (pinfunction "NC_C8") (pintype "passive"))
    )
    (net (code "73") (name "unconnected-(X1-RST-PadC2)") (class "Default")
      (node (ref "X1") (pin "C2") (pinfunction "RST_C2") (pintype "passive"))
    )
    (net (code "74") (name "unconnected-(X1-VCC-PadC1)") (class "Default")
      (node (ref "X1") (pin "C1") (pinfunction "VCC_C1") (pintype "passive"))
    )
  )
)
